# question_2.net
KiCad netlist of a schematic drawn in EAGLE
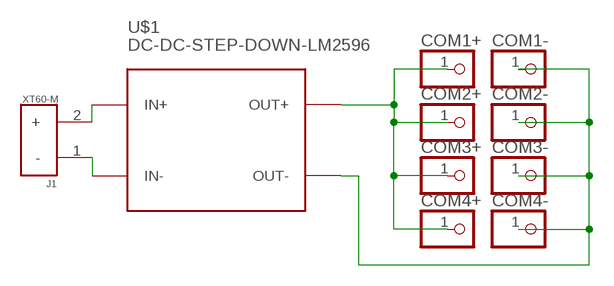
[diagram p0: schematic, sheet 1]

(export (version "E")
  (design (tool "Eeschema 10.0.6"))
  (components
    (comp (ref "COM1+")
      (value "PINHD-1X1")
      (footprint "eagle-import:1X01")
      (libsource (lib "eagle-import") (part "PINHD-1X1"))
    )
    (comp (ref "COM1-")
      (value "PINHD-1X1")
      (footprint "eagle-import:1X01")
      (libsource (lib "eagle-import") (part "PINHD-1X1"))
    )
    (comp (ref "COM2+")
      (value "PINHD-1X1")
      (footprint "eagle-import:1X01")
      (libsource (lib "eagle-import") (part "PINHD-1X1"))
    )
    (comp (ref "COM2-")
      (value "PINHD-1X1")
      (footprint "eagle-import:1X01")
      (libsource (lib "eagle-import") (part "PINHD-1X1"))
    )
    (comp (ref "COM3+")
      (value "PINHD-1X1")
      (footprint "eagle-import:1X01")
      (libsource (lib "eagle-import") (part "PINHD-1X1"))
    )
    (comp (ref "COM3-")
      (value "PINHD-1X1")
      (footprint "eagle-import:1X01")
      (libsource (lib "eagle-import") (part "PINHD-1X1"))
    )
    (comp (ref "COM4+")
      (value "PINHD-1X1")
      (footprint "eagle-import:1X01")
      (libsource (lib "eagle-import") (part "PINHD-1X1"))
    )
    (comp (ref "COM4-")
      (value "PINHD-1X1")
      (footprint "eagle-import:1X01")
      (libsource (lib "eagle-import") (part "PINHD-1X1"))
    )
    (comp (ref "J1")
      (value "XT60-M")
      (footprint "eagle-import:AMASS_XT60-M")
      (fields (field (name "MF") "AMASS"))
      (libsource (lib "eagle-import") (part "XT60-M"))
    )
    (comp (ref "U$1")
      (value "DC-DC-STEP-DOWN-LM2596")
      (footprint "eagle-import:DC-DC-STEP-DOWN-LM2596")
      (libsource (lib "eagle-import") (part "DC-DC-STEP-DOWN-LM2596"))
    )
  )
  (nets
    (net (code "1") (name "Net-(COM1+-Pad1)") (class "Default")
      (node (ref "COM1+") (pin "1") (pinfunction "1_1") (pintype "passive"))
      (node (ref "COM2+") (pin "1") (pinfunction "1_1") (pintype "passive"))
      (node (ref "COM3+") (pin "1") (pinfunction "1_1") (pintype "passive"))
      (node (ref "COM4+") (pin "1") (pinfunction "1_1") (pintype "passive"))
      (node (ref "U$1") (pin "OUT+") (pinfunction "OUT+_OUT+") (pintype "bidirectional"))
    )
    (net (code "2") (name "Net-(COM1--Pad1)") (class "Default")
      (node (ref "COM1-") (pin "1") (pinfunction "1_1") (pintype "passive"))
      (node (ref "COM2-") (pin "1") (pinfunction "1_1") (pintype "passive"))
      (node (ref "COM3-") (pin "1") (pinfunction "1_1") (pintype "passive"))
      (node (ref "COM4-") (pin "1") (pinfunction "1_1") (pintype "passive"))
      (node (ref "U$1") (pin "OUT-") (pinfunction "OUT-_OUT-") (pintype "bidirectional"))
    )
    (net (code "3") (name "Net-(J1-+)") (class "Default")
      (node (ref "J1") (pin "2") (pinfunction "+_2") (pintype "passive"))
      (node (ref "U$1") (pin "IN+") (pinfunction "IN+_IN+") (pintype "bidirectional"))
    )
    (net (code "4") (name "Net-(J1--)") (class "Default")
      (node (ref "J1") (pin "1") (pinfunction "-_1") (pintype "passive"))
      (node (ref "U$1") (pin "IN-") (pinfunction "IN-_IN-") (pintype "bidirectional"))
    )
  )
)
